# 12_USB3_0_Connector1_2.net
KiCad netlist of a schematic drawn in Altium Designer
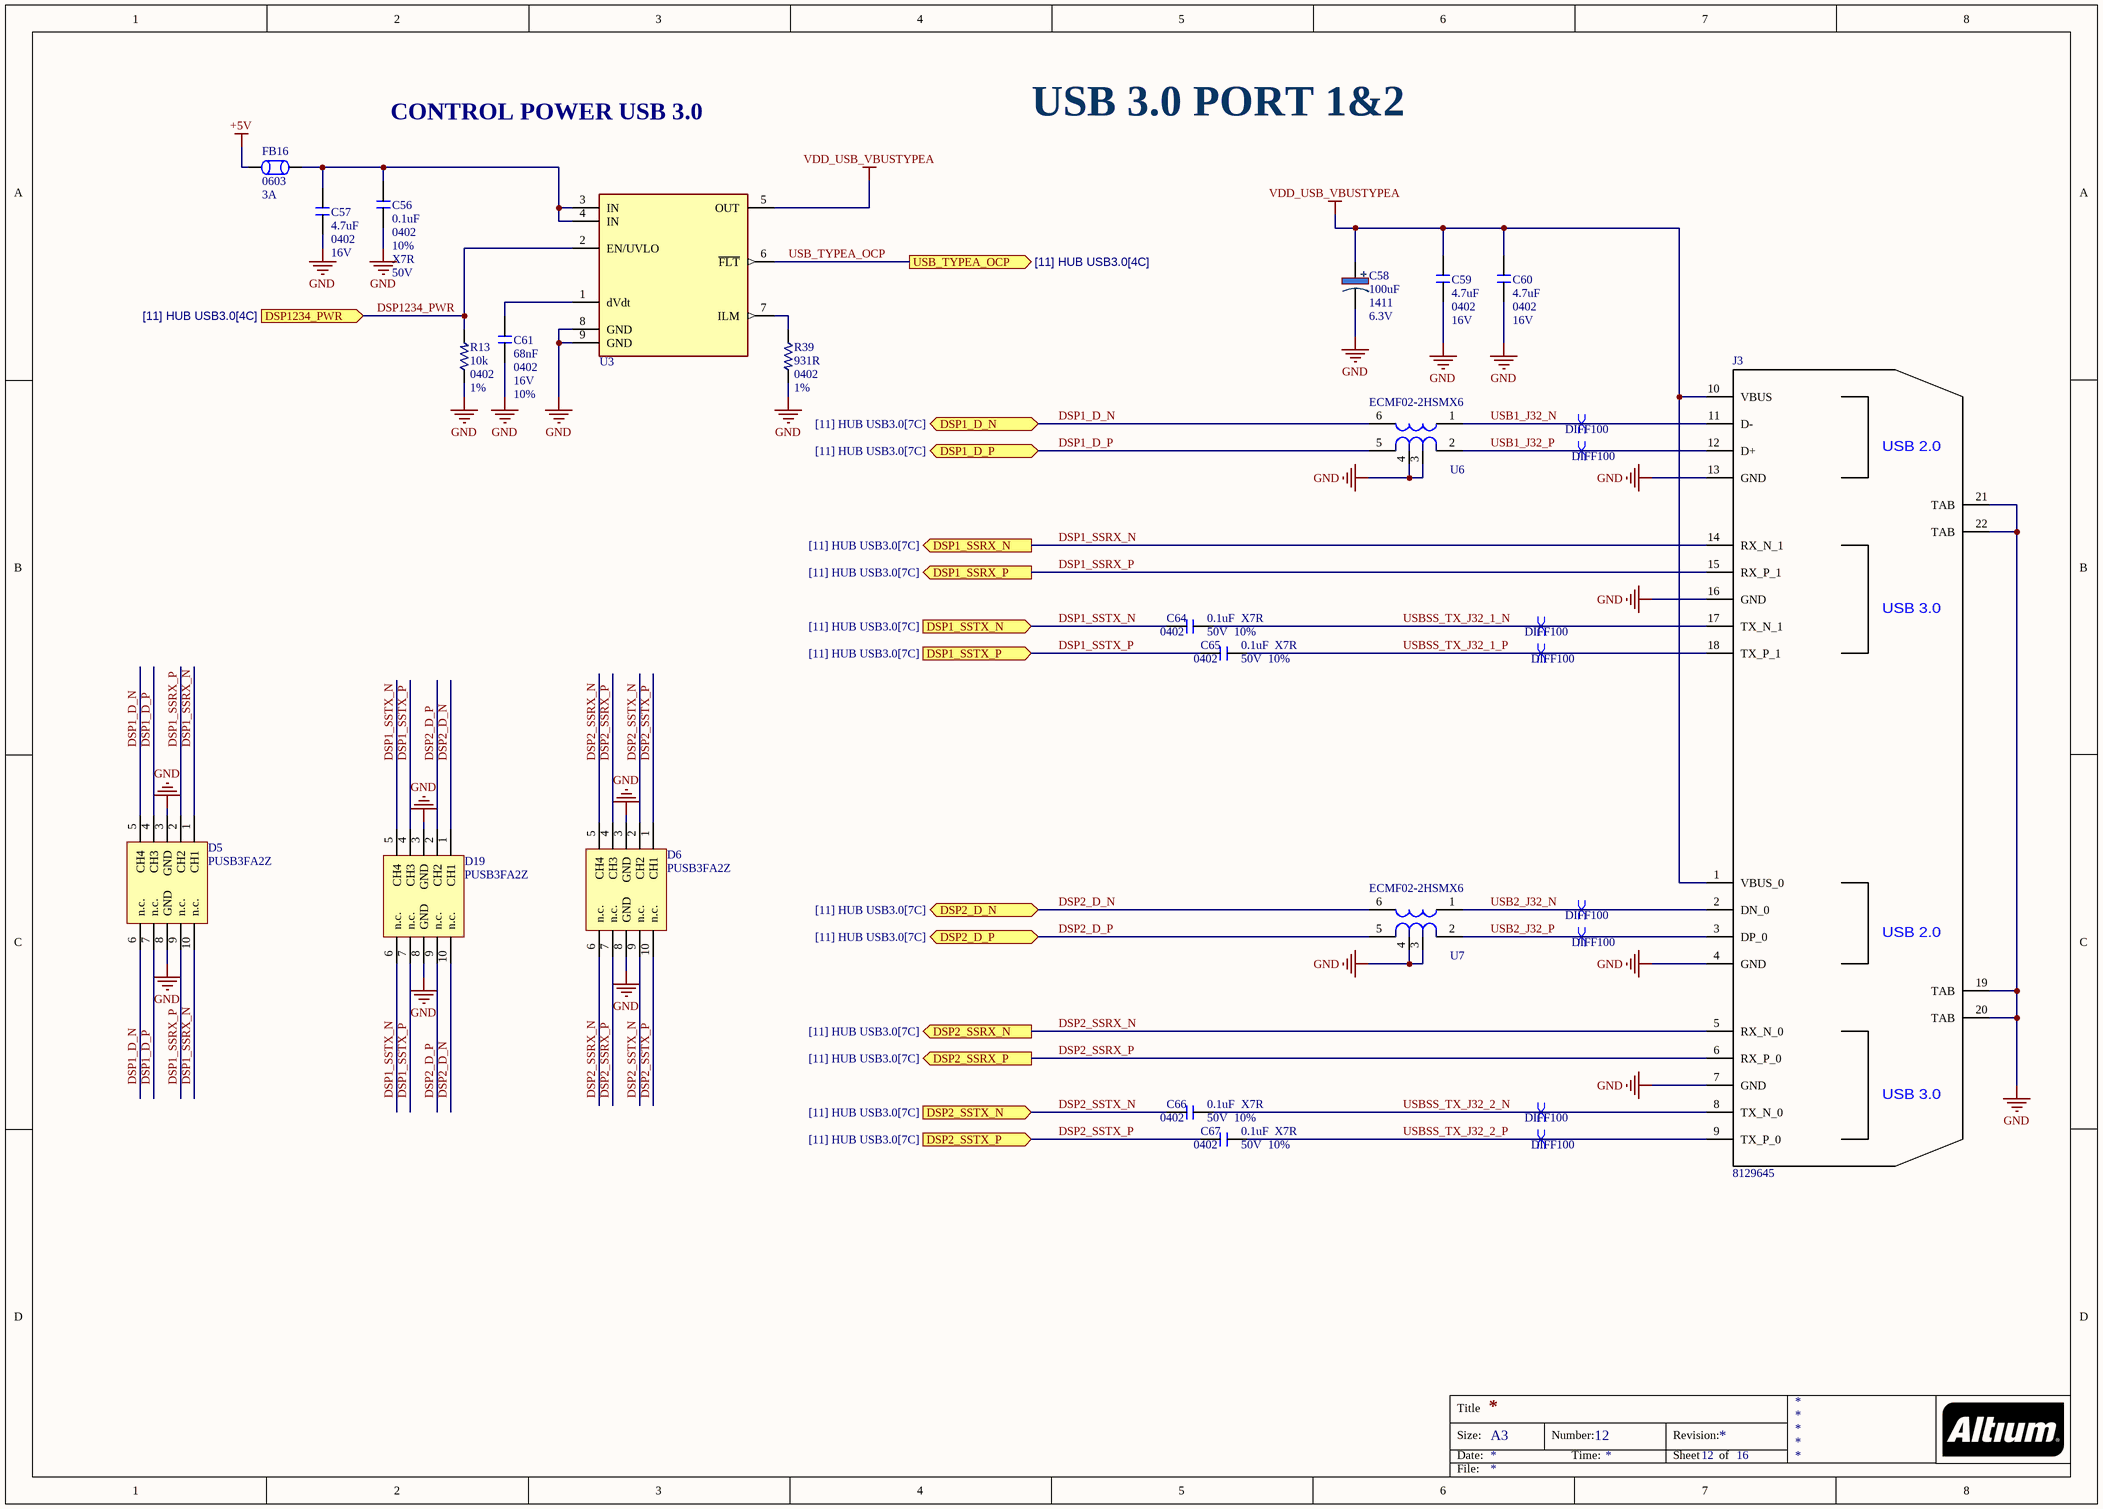
[diagram p0: [12] USB3.0_Connector1&2.SchDoc]

(export (version "E")
  (design (tool "Eeschema 10.0.6"))
  (components
    (comp (ref "C56")
      (value "0.1uF")
      (footprint "C0402M")
      (description "CAP CER 0.1UF 50V X7R 0402")
      (fields
        (field (name "MANUFACTURER") "Murata")
        (field (name "MANUFACTURER PART NUMBER") "GRM155R71H104KE14D")
        (field (name "CASE/PACKAGE") "0402")
        (field (name "TOLERANCE") "10%")
        (field (name "DIELECTRIC") "X7R")
        (field (name "VOLTAGE") "50V")
      )
      (libsource (lib "CommonLib") (part "CAP_CER"))
    )
    (comp (ref "C57")
      (value "4.7uF")
      (footprint "C0402M")
      (description "CAP CER 4.7UF 16V X5R 0402")
      (fields
        (field (name "MANUFACTURER") "Samsung")
        (field (name "MANUFACTURER PART NUMBER") "CL05A475MO5NUNC")
        (field (name "CASE/PACKAGE") "0402")
        (field (name "VOLTAGE RATING") "16V")
      )
      (libsource (lib "CommonLib") (part "CAP_CER"))
    )
    (comp (ref "C58")
      (value "100uF")
      (footprint "CP_TANT_3528")
      (description "CAP TANT 100UF 20% 6.3V 1411")
      (fields
        (field (name "MANUFACTURER") "KEMET")
        (field (name "MANUFACTURER PART NUMBER") "T495B107M006ATE700")
        (field (name "CASE/PACKAGE") "1411")
        (field (name "VOLTAGE RATING") "6.3V")
      )
      (libsource (lib "CommonLib") (part "CAP_PL"))
    )
    (comp (ref "C59")
      (value "4.7uF")
      (footprint "C0402M")
      (description "CAP CER 4.7UF 16V X5R 0402")
      (fields
        (field (name "MANUFACTURER") "Samsung")
        (field (name "MANUFACTURER PART NUMBER") "CL05A475MO5NUNC")
        (field (name "CASE/PACKAGE") "0402")
        (field (name "VOLTAGE RATING") "16V")
      )
      (libsource (lib "CommonLib") (part "CAP_CER"))
    )
    (comp (ref "C60")
      (value "4.7uF")
      (footprint "C0402M")
      (description "CAP CER 4.7UF 16V X5R 0402")
      (fields
        (field (name "MANUFACTURER") "Samsung")
        (field (name "MANUFACTURER PART NUMBER") "CL05A475MO5NUNC")
        (field (name "CASE/PACKAGE") "0402")
        (field (name "VOLTAGE RATING") "16V")
      )
      (libsource (lib "CommonLib") (part "CAP_CER"))
    )
    (comp (ref "C61")
      (value "68nF")
      (footprint "C0402M")
      (description "CAP .068UF 16VDC X7R 10% SMD  0402")
      (fields
        (field (name "CASE/PACKAGE") "0402")
        (field (name "VOLTAGE RATING") "16V")
        (field (name "TOLERANCE") "10%")
      )
      (libsource (lib "CommonLib") (part "CAP_CER"))
    )
    (comp (ref "C64")
      (value "0.1uF")
      (footprint "C0402M")
      (description "CAP CER 0.1UF 50V X7R 0402")
      (fields
        (field (name "MANUFACTURER") "Murata")
        (field (name "MANUFACTURER PART NUMBER") "GRM155R71H104KE14D")
        (field (name "CASE/PACKAGE") "0402")
        (field (name "TOLERANCE") "10%")
        (field (name "DIELECTRIC") "X7R")
        (field (name "VOLTAGE") "50V")
      )
      (libsource (lib "CommonLib") (part "CAP_CER"))
    )
    (comp (ref "C65")
      (value "0.1uF")
      (footprint "C0402M")
      (description "CAP CER 0.1UF 50V X7R 0402")
      (fields
        (field (name "MANUFACTURER") "Murata")
        (field (name "MANUFACTURER PART NUMBER") "GRM155R71H104KE14D")
        (field (name "CASE/PACKAGE") "0402")
        (field (name "TOLERANCE") "10%")
        (field (name "DIELECTRIC") "X7R")
        (field (name "VOLTAGE") "50V")
      )
      (libsource (lib "CommonLib") (part "CAP_CER"))
    )
    (comp (ref "C66")
      (value "0.1uF")
      (footprint "C0402M")
      (description "CAP CER 0.1UF 50V X7R 0402")
      (fields
        (field (name "MANUFACTURER") "Murata")
        (field (name "MANUFACTURER PART NUMBER") "GRM155R71H104KE14D")
        (field (name "CASE/PACKAGE") "0402")
        (field (name "TOLERANCE") "10%")
        (field (name "DIELECTRIC") "X7R")
        (field (name "VOLTAGE") "50V")
      )
      (libsource (lib "CommonLib") (part "CAP_CER"))
    )
    (comp (ref "C67")
      (value "0.1uF")
      (footprint "C0402M")
      (description "CAP CER 0.1UF 50V X7R 0402")
      (fields
        (field (name "MANUFACTURER") "Murata")
        (field (name "MANUFACTURER PART NUMBER") "GRM155R71H104KE14D")
        (field (name "CASE/PACKAGE") "0402")
        (field (name "TOLERANCE") "10%")
        (field (name "DIELECTRIC") "X7R")
        (field (name "VOLTAGE") "50V")
      )
      (libsource (lib "CommonLib") (part "CAP_CER"))
    )
    (comp (ref "D5")
      (value "PUSB3FA2Z")
      (footprint "SON50P100X50-10N")
      (description "ESD Suppressors / TVS Diodes PUSB3FA2 XSON10")
      (libsource (lib "Nauvus") (part "PUSB3FA2Z"))
    )
    (comp (ref "D6")
      (value "PUSB3FA2Z")
      (footprint "SON50P100X50-10N")
      (description "ESD Suppressors / TVS Diodes PUSB3FA2 XSON10")
      (libsource (lib "Nauvus") (part "PUSB3FA2Z"))
    )
    (comp (ref "D19")
      (value "PUSB3FA2Z")
      (footprint "SON50P100X50-10N")
      (description "ESD Suppressors / TVS Diodes PUSB3FA2 XSON10")
      (libsource (lib "Nauvus") (part "PUSB3FA2Z"))
    )
    (comp (ref "FB16")
      (value "FB")
      (footprint "R0603M")
      (fields
        (field (name "CASE/PACKAGE") "0603")
        (field (name "TOLERANCE") "25%")
        (field (name "MAX DC CURRENT") "3A")
      )
      (libsource (lib "CommonLib") (part "FB"))
    )
    (comp (ref "J3")
      (value "48406-0003")
      (footprint "Molex_48406-0003_0")
      (description "Conn USB 3.0 Type A F 18 POS 2mm/2.5mm Solder RA Thru-Hole 18 Terminal 2 Port USB 3.0 Tray")
      (fields (field (name "SUPPLIER PART NUMBER 1") "8129645"))
      (libsource (lib "Schlib1") (part "48406-0003"))
    )
    (comp (ref "R13")
      (value "10k")
      (footprint "R0402M")
      (description "RES SMD 10K OHM 1% 1/16W 0402")
      (fields
        (field (name "MANUFACTURER") "Yageo")
        (field (name "MANUFACTURER PART NUMBER") "RC0402FR-0710KL")
        (field (name "CASE CODE (IMPERIAL)") "0402")
        (field (name "TOLERANCE") "1%")
      )
      (libsource (lib "CommonLib") (part "RES_SMD"))
    )
    (comp (ref "R39")
      (value "931R")
      (footprint "R0402M")
      (description "贴片电阻 931Ω ± 1.00% 0.0625W ± 100ppm/℃ 0402")
      (fields (field (name "CASE CODE (IMPERIAL)") "0402") (field (name "TOLERANCE") "1%"))
      (libsource (lib "CommonLib") (part "RES_SMD"))
    )
    (comp (ref "U3")
      (value "TPS259530DSGT")
      (footprint "TPS259530DSGT")
      (description "TPS259530 12V eFuse with Fast Overvoltage Protection 2.7V to 18V 4A 34m Ohm 8-Pin WSON T/R")
      (libsource (lib "Schlib1") (part "TPS259530DSGT"))
    )
    (comp (ref "U6")
      (value "ECMF02-2HSMX6")
      (footprint "SON50P150X55-6N")
      (description "CMC 200MA 2LN SMD ESD")
      (libsource (lib "Nauvus") (part "ECMF02-2AMX6"))
    )
    (comp (ref "U7")
      (value "ECMF02-2HSMX6")
      (footprint "SON50P150X55-6N")
      (description "CMC 200MA 2LN SMD ESD")
      (libsource (lib "Nauvus") (part "ECMF02-2AMX6"))
    )
  )
  (nets
    (net (code "1") (name "+5V") (class "Default")
      (node (ref "FB16") (pin "2") (pinfunction "2_2") (pintype "passive"))
    )
    (net (code "2") (name "/DSP1_D_N") (class "Default")
      (node (ref "D5") (pin "5") (pinfunction "CH4_5") (pintype "passive"))
      (node (ref "D5") (pin "6") (pinfunction "n.c._6") (pintype "passive"))
      (node (ref "U6") (pin "6") (pinfunction "6_6") (pintype "passive"))
    )
    (net (code "3") (name "/DSP1_D_P") (class "Default")
      (node (ref "D5") (pin "4") (pinfunction "CH3_4") (pintype "passive"))
      (node (ref "D5") (pin "7") (pinfunction "n.c._7") (pintype "passive"))
      (node (ref "U6") (pin "5") (pinfunction "5_5") (pintype "passive"))
    )
    (net (code "4") (name "/DSP1_SSRX_N") (class "Default")
      (node (ref "D5") (pin "1") (pinfunction "CH1_1") (pintype "passive"))
      (node (ref "D5") (pin "10") (pinfunction "n.c._10") (pintype "passive"))
      (node (ref "J3") (pin "14") (pinfunction "RX_N_1_14") (pintype "passive"))
    )
    (net (code "5") (name "/DSP1_SSRX_P") (class "Default")
      (node (ref "D5") (pin "2") (pinfunction "CH2_2") (pintype "passive"))
      (node (ref "D5") (pin "9") (pinfunction "n.c._9") (pintype "passive"))
      (node (ref "J3") (pin "15") (pinfunction "RX_P_1_15") (pintype "passive"))
    )
    (net (code "6") (name "/DSP1_SSTX_N") (class "Default")
      (node (ref "C64") (pin "1") (pinfunction "1_1") (pintype "passive"))
      (node (ref "D19") (pin "5") (pinfunction "CH4_5") (pintype "passive"))
      (node (ref "D19") (pin "6") (pinfunction "n.c._6") (pintype "passive"))
    )
    (net (code "7") (name "/DSP1_SSTX_P") (class "Default")
      (node (ref "C65") (pin "1") (pinfunction "1_1") (pintype "passive"))
      (node (ref "D19") (pin "4") (pinfunction "CH3_4") (pintype "passive"))
      (node (ref "D19") (pin "7") (pinfunction "n.c._7") (pintype "passive"))
    )
    (net (code "8") (name "/DSP2_D_N") (class "Default")
      (node (ref "D19") (pin "1") (pinfunction "CH1_1") (pintype "passive"))
      (node (ref "D19") (pin "10") (pinfunction "n.c._10") (pintype "passive"))
      (node (ref "U7") (pin "6") (pinfunction "6_6") (pintype "passive"))
    )
    (net (code "9") (name "/DSP2_D_P") (class "Default")
      (node (ref "D19") (pin "2") (pinfunction "CH2_2") (pintype "passive"))
      (node (ref "D19") (pin "9") (pinfunction "n.c._9") (pintype "passive"))
      (node (ref "U7") (pin "5") (pinfunction "5_5") (pintype "passive"))
    )
    (net (code "10") (name "/DSP2_SSRX_N") (class "Default")
      (node (ref "D6") (pin "5") (pinfunction "CH4_5") (pintype "passive"))
      (node (ref "D6") (pin "6") (pinfunction "n.c._6") (pintype "passive"))
      (node (ref "J3") (pin "5") (pinfunction "RX_N_0_5") (pintype "passive"))
    )
    (net (code "11") (name "/DSP2_SSRX_P") (class "Default")
      (node (ref "D6") (pin "4") (pinfunction "CH3_4") (pintype "passive"))
      (node (ref "D6") (pin "7") (pinfunction "n.c._7") (pintype "passive"))
      (node (ref "J3") (pin "6") (pinfunction "RX_P_0_6") (pintype "passive"))
    )
    (net (code "12") (name "/DSP2_SSTX_N") (class "Default")
      (node (ref "C66") (pin "1") (pinfunction "1_1") (pintype "passive"))
      (node (ref "D6") (pin "2") (pinfunction "CH2_2") (pintype "passive"))
      (node (ref "D6") (pin "9") (pinfunction "n.c._9") (pintype "passive"))
    )
    (net (code "13") (name "/DSP2_SSTX_P") (class "Default")
      (node (ref "C67") (pin "1") (pinfunction "1_1") (pintype "passive"))
      (node (ref "D6") (pin "1") (pinfunction "CH1_1") (pintype "passive"))
      (node (ref "D6") (pin "10") (pinfunction "n.c._10") (pintype "passive"))
    )
    (net (code "14") (name "/DSP1234_PWR") (class "Default")
      (node (ref "R13") (pin "1") (pinfunction "1_1") (pintype "passive"))
      (node (ref "U3") (pin "2") (pinfunction "EN/UVLO_2") (pintype "passive"))
    )
    (net (code "15") (name "/USB1_J32_N") (class "Default")
      (node (ref "J3") (pin "11") (pinfunction "D-_11") (pintype "passive"))
      (node (ref "U6") (pin "1") (pinfunction "1_1") (pintype "passive"))
    )
    (net (code "16") (name "/USB1_J32_P") (class "Default")
      (node (ref "J3") (pin "12") (pinfunction "D+_12") (pintype "passive"))
      (node (ref "U6") (pin "2") (pinfunction "2_2") (pintype "passive"))
    )
    (net (code "17") (name "/USB2_J32_N") (class "Default")
      (node (ref "J3") (pin "2") (pinfunction "DN_0_2") (pintype "passive"))
      (node (ref "U7") (pin "1") (pinfunction "1_1") (pintype "passive"))
    )
    (net (code "18") (name "/USB2_J32_P") (class "Default")
      (node (ref "J3") (pin "3") (pinfunction "DP_0_3") (pintype "passive"))
      (node (ref "U7") (pin "2") (pinfunction "2_2") (pintype "passive"))
    )
    (net (code "19") (name "/USBSS_TX_J32_1_N") (class "Default")
      (node (ref "C64") (pin "2") (pinfunction "2_2") (pintype "passive"))
      (node (ref "J3") (pin "17") (pinfunction "TX_N_1_17") (pintype "passive"))
    )
    (net (code "20") (name "/USBSS_TX_J32_1_P") (class "Default")
      (node (ref "C65") (pin "2") (pinfunction "2_2") (pintype "passive"))
      (node (ref "J3") (pin "18") (pinfunction "TX_P_1_18") (pintype "passive"))
    )
    (net (code "21") (name "/USBSS_TX_J32_2_N") (class "Default")
      (node (ref "C66") (pin "2") (pinfunction "2_2") (pintype "passive"))
      (node (ref "J3") (pin "8") (pinfunction "TX_N_0_8") (pintype "passive"))
    )
    (net (code "22") (name "/USBSS_TX_J32_2_P") (class "Default")
      (node (ref "C67") (pin "2") (pinfunction "2_2") (pintype "passive"))
      (node (ref "J3") (pin "9") (pinfunction "TX_P_0_9") (pintype "passive"))
    )
    (net (code "23") (name "/USB_TYPEA_OCP") (class "Default")
      (node (ref "U3") (pin "6") (pinfunction "~{FLT}_6") (pintype "output"))
    )
    (net (code "24") (name "GND") (class "Default")
      (node (ref "C56") (pin "1") (pinfunction "1_1") (pintype "passive"))
      (node (ref "C57") (pin "2") (pinfunction "2_2") (pintype "passive"))
      (node (ref "C58") (pin "2") (pinfunction "2_2") (pintype "passive"))
      (node (ref "C59") (pin "2") (pinfunction "2_2") (pintype "passive"))
      (node (ref "C60") (pin "2") (pinfunction "2_2") (pintype "passive"))
      (node (ref "C61") (pin "1") (pinfunction "1_1") (pintype "passive"))
      (node (ref "D19") (pin "3") (pinfunction "GND_3") (pintype "passive"))
      (node (ref "D19") (pin "8") (pinfunction "GND_8") (pintype "passive"))
      (node (ref "D5") (pin "3") (pinfunction "GND_3") (pintype "passive"))
      (node (ref "D5") (pin "8") (pinfunction "GND_8") (pintype "passive"))
      (node (ref "D6") (pin "3") (pinfunction "GND_3") (pintype "passive"))
      (node (ref "D6") (pin "8") (pinfunction "GND_8") (pintype "passive"))
      (node (ref "J3") (pin "13") (pinfunction "GND_13") (pintype "power_in"))
      (node (ref "J3") (pin "16") (pinfunction "GND_16") (pintype "passive"))
      (node (ref "J3") (pin "19") (pinfunction "TAB_19") (pintype "passive"))
      (node (ref "J3") (pin "20") (pinfunction "TAB_20") (pintype "passive"))
      (node (ref "J3") (pin "21") (pinfunction "TAB_21") (pintype "passive"))
      (node (ref "J3") (pin "22") (pinfunction "TAB_22") (pintype "passive"))
      (node (ref "J3") (pin "4") (pinfunction "GND_4") (pintype "passive"))
      (node (ref "J3") (pin "7") (pinfunction "GND_7") (pintype "passive"))
      (node (ref "R13") (pin "2") (pinfunction "2_2") (pintype "passive"))
      (node (ref "R39") (pin "1") (pinfunction "1_1") (pintype "passive"))
      (node (ref "U3") (pin "8") (pinfunction "GND_8") (pintype "power_in"))
      (node (ref "U3") (pin "9") (pinfunction "GND_9") (pintype "power_in"))
      (node (ref "U6") (pin "3") (pinfunction "3_3") (pintype "passive"))
      (node (ref "U6") (pin "4") (pinfunction "4_4") (pintype "passive"))
      (node (ref "U7") (pin "3") (pinfunction "3_3") (pintype "passive"))
      (node (ref "U7") (pin "4") (pinfunction "4_4") (pintype "passive"))
    )
    (net (code "25") (name "Net-(C56-Pad2)") (class "Default")
      (node (ref "C56") (pin "2") (pinfunction "2_2") (pintype "passive"))
      (node (ref "C57") (pin "1") (pinfunction "1_1") (pintype "passive"))
      (node (ref "FB16") (pin "1") (pinfunction "1_1") (pintype "passive"))
      (node (ref "U3") (pin "3") (pinfunction "IN_3") (pintype "power_in"))
      (node (ref "U3") (pin "4") (pinfunction "IN_4") (pintype "power_in"))
    )
    (net (code "26") (name "Net-(U3-ILM)") (class "Default")
      (node (ref "R39") (pin "2") (pinfunction "2_2") (pintype "passive"))
      (node (ref "U3") (pin "7") (pinfunction "ILM_7") (pintype "output"))
    )
    (net (code "27") (name "Net-(U3-dVdt)") (class "Default")
      (node (ref "C61") (pin "2") (pinfunction "2_2") (pintype "passive"))
      (node (ref "U3") (pin "1") (pinfunction "dVdt_1") (pintype "passive"))
    )
    (net (code "28") (name "VDD_USB_VBUSTYPEA") (class "Default")
      (node (ref "C58") (pin "1") (pinfunction "1_1") (pintype "passive"))
      (node (ref "C59") (pin "1") (pinfunction "1_1") (pintype "passive"))
      (node (ref "C60") (pin "1") (pinfunction "1_1") (pintype "passive"))
      (node (ref "J3") (pin "1") (pinfunction "VBUS_0_1") (pintype "passive"))
      (node (ref "J3") (pin "10") (pinfunction "VBUS_10") (pintype "power_in"))
      (node (ref "U3") (pin "5") (pinfunction "OUT_5") (pintype "power_in"))
    )
  )
)
